# 12_to_24V_boost_tps5534.net
KiCad netlist of a schematic drawn in Altium Designer
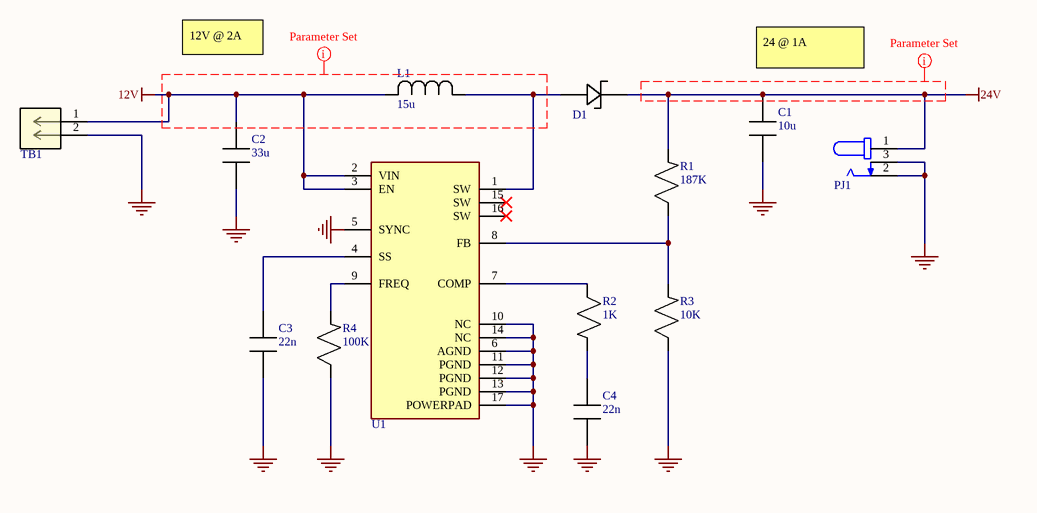
[diagram p0: 12_to_24V_boost_tps5534.SchDoc]

(export (version "E")
  (design (tool "Eeschema 10.0.6"))
  (components
    (comp (ref "C1")
      (value "10u")
      (footprint "CAP_0603")
      (description "CAP CER 10UF 10V X5R 0603")
      (fields (field (name "MANUFACTURER") "Samsung Electro-Mechanics"))
      (libsource (lib "General_Components") (part "CAP_10u_0603"))
    )
    (comp (ref "C2")
      (value "33u")
      (footprint "CAP_0805")
      (description "CAP CER 33UF 6.3V X5R 0805")
      (fields (field (name "MANUFACTURER") "TDK Corporation"))
      (libsource (lib "General_Components") (part "CAP_33u_0805"))
    )
    (comp (ref "C3")
      (value "22n")
      (footprint "CAP_0603")
      (description "CAP CER 0.027UF 25V X7R 0603")
      (fields (field (name "MANUFACTURER") "Cal-Chip Electronics, Inc.") (field (name "Comment") "22nF"))
      (libsource (lib "General_Components") (part "CAP_22nF_0603"))
    )
    (comp (ref "C4")
      (value "22n")
      (footprint "CAP_0603")
      (description "CAP CER 0.027UF 25V X7R 0603")
      (fields (field (name "MANUFACTURER") "Cal-Chip Electronics, Inc.") (field (name "Comment") "22nF"))
      (libsource (lib "General_Components") (part "CAP_22nF_0603"))
    )
    (comp (ref "D1")
      (value "SS3P4-M3/84A")
      (footprint "DO-220AA(POWER DIODE)")
      (description "DIODE SCHOTTKY 40V 3A DO220AA")
      (fields (field (name "MANUFACTURER") "Vishay General Semiconductor - Diodes Division"))
      (libsource (lib "General_Components") (part "SS3P4-M3/84A"))
    )
    (comp (ref "L1")
      (value "15u")
      (footprint "L_0603")
      (description "FIXED IND 15UH 2MA 1.5 OHM SMD")
      (fields (field (name "MANUFACTURER") "TDK Corporation") (field (name "Comment") "IND 15UH 2MA 1.5 OHM"))
      (libsource (lib "General_Components") (part "L_15uH_0603"))
    )
    (comp (ref "PJ1")
      (value "CONN PWR JACK 2.5X5.5MM SOLDER")
      (footprint "PWR_JACK_2.50mm")
      (description "Power Barrel Connector Jack 2.50mm ID (0.098\"), 5.50mm OD (0.217\") Through Hole, Right Angle")
      (fields (field (name "MANUFACTURER") "Same Sky (Formerly CUI Devices)"))
      (libsource (lib "General_Components") (part "PWR_JACK_2.50mm"))
    )
    (comp (ref "R1")
      (value "187K")
      (footprint "RES_0603")
      (description "RES SMD 187K OHM 1% 1/10W 0603")
      (fields (field (name "MANUFACTURER") "Panasonic Electronic Components"))
      (libsource (lib "General_Components") (part "RES_187K_0603"))
    )
    (comp (ref "R2")
      (value "1K")
      (footprint "RES_0603")
      (description "RES 1K OHM 1% 1/10W 0603")
      (fields (field (name "MANUFACTURER") "Stackpole Electronics Inc"))
      (libsource (lib "General_Components") (part "RES_1K_0603"))
    )
    (comp (ref "R3")
      (value "10K")
      (footprint "RES_0603")
      (description "RES 10K OHM 1% 1/10W 0603")
      (fields (field (name "MANUFACTURER") "Stackpole Electronics Inc"))
      (libsource (lib "General_Components") (part "RES_10K_0603"))
    )
    (comp (ref "R4")
      (value "100K")
      (footprint "RES_0603")
      (fields (field (name "MANUFACTURER") "Stackpole Electronics Inc"))
      (libsource (lib "General_Components") (part "RES_100K_0603"))
    )
    (comp (ref "TB1")
      (value "TERM BLK 2P SIDE ENT 5.08MM PCB")
      (footprint "TB_2x1_5.08mm")
      (description "2 Bloques de terminales - Cable a placa Horizontal con placa 0.200\" (5.08mm) Orificio pasante")
      (fields (field (name "MANUFACTURER") "Weidmüller"))
      (libsource (lib "General_Components") (part "TB_2x1_5.08mm"))
    )
    (comp (ref "U1")
      (value "TPS55340RTER")
      (footprint "WQFN-16_3X3MM")
      (description "IC REG BOOST ADJ 5.25A 16WQFN")
      (fields (field (name "MANUFACTURER") "Texas Instruments"))
      (libsource (lib "General_Components") (part "TPS55340RTER"))
    )
  )
  (nets
    (net (code "1") (name "12V") (class "Default")
      (node (ref "C2") (pin "2") (pinfunction "2_2") (pintype "passive"))
      (node (ref "L1") (pin "1") (pinfunction "1_1") (pintype "passive"))
      (node (ref "TB1") (pin "1") (pinfunction "1_1") (pintype "passive"))
      (node (ref "U1") (pin "2") (pinfunction "VIN_2") (pintype "power_in"))
      (node (ref "U1") (pin "3") (pinfunction "EN_3") (pintype "passive"))
    )
    (net (code "2") (name "24V") (class "Default")
      (node (ref "C1") (pin "2") (pinfunction "2_2") (pintype "passive"))
      (node (ref "D1") (pin "2") (pinfunction "2_2") (pintype "passive"))
      (node (ref "PJ1") (pin "1") (pinfunction "1_1") (pintype "passive"))
      (node (ref "R1") (pin "2") (pintype "passive"))
    )
    (net (code "3") (name "GND") (class "Default")
      (node (ref "C1") (pin "1") (pinfunction "1_1") (pintype "passive"))
      (node (ref "C2") (pin "1") (pinfunction "1_1") (pintype "passive"))
      (node (ref "C3") (pin "1") (pinfunction "1_1") (pintype "passive"))
      (node (ref "C4") (pin "1") (pinfunction "1_1") (pintype "passive"))
      (node (ref "PJ1") (pin "2") (pinfunction "2_2") (pintype "passive"))
      (node (ref "PJ1") (pin "3") (pinfunction "3_3") (pintype "passive"))
      (node (ref "R3") (pin "1") (pintype "passive"))
      (node (ref "R4") (pin "1") (pintype "passive"))
      (node (ref "TB1") (pin "2") (pinfunction "2_2") (pintype "passive"))
      (node (ref "U1") (pin "10") (pinfunction "NC_10") (pintype "power_in"))
      (node (ref "U1") (pin "11") (pinfunction "PGND_11") (pintype "power_in"))
      (node (ref "U1") (pin "12") (pinfunction "PGND_12") (pintype "power_in"))
      (node (ref "U1") (pin "13") (pinfunction "PGND_13") (pintype "power_in"))
      (node (ref "U1") (pin "14") (pinfunction "NC_14") (pintype "power_in"))
      (node (ref "U1") (pin "17") (pinfunction "POWERPAD_17") (pintype "power_in"))
      (node (ref "U1") (pin "5") (pinfunction "SYNC_5") (pintype "passive"))
      (node (ref "U1") (pin "6") (pinfunction "AGND_6") (pintype "power_in"))
    )
    (net (code "4") (name "Net-(D1-Pad1)") (class "Default")
      (node (ref "D1") (pin "1") (pinfunction "1_1") (pintype "passive"))
      (node (ref "L1") (pin "2") (pinfunction "2_2") (pintype "passive"))
      (node (ref "U1") (pin "1") (pinfunction "SW_1") (pintype "passive"))
    )
    (net (code "5") (name "Net-(R2-__2)") (class "Default")
      (node (ref "C4") (pin "2") (pinfunction "2_2") (pintype "passive"))
      (node (ref "R2") (pin "2") (pinfunction "__2_2") (pintype "passive"))
    )
    (net (code "6") (name "Net-(U1-COMP)") (class "Default")
      (node (ref "R2") (pin "1") (pinfunction "1_1") (pintype "passive"))
      (node (ref "U1") (pin "7") (pinfunction "COMP_7") (pintype "passive"))
    )
    (net (code "7") (name "Net-(U1-FB)") (class "Default")
      (node (ref "R1") (pin "1") (pintype "passive"))
      (node (ref "R3") (pin "2") (pintype "passive"))
      (node (ref "U1") (pin "8") (pinfunction "FB_8") (pintype "passive"))
    )
    (net (code "8") (name "Net-(U1-FREQ)") (class "Default")
      (node (ref "R4") (pin "2") (pintype "passive"))
      (node (ref "U1") (pin "9") (pinfunction "FREQ_9") (pintype "passive"))
    )
    (net (code "9") (name "Net-(U1-SS)") (class "Default")
      (node (ref "C3") (pin "2") (pinfunction "2_2") (pintype "passive"))
      (node (ref "U1") (pin "4") (pinfunction "SS_4") (pintype "passive"))
    )
    (net (code "10") (name "unconnected-(U1-SW-Pad15)") (class "Default")
      (node (ref "U1") (pin "15") (pinfunction "SW_15") (pintype "passive+no_connect"))
    )
    (net (code "11") (name "unconnected-(U1-SW-Pad16)") (class "Default")
      (node (ref "U1") (pin "16") (pinfunction "SW_16") (pintype "passive+no_connect"))
    )
  )
)
